# rf-mixer.net
KiCad netlist of a schematic drawn in Altium Designer
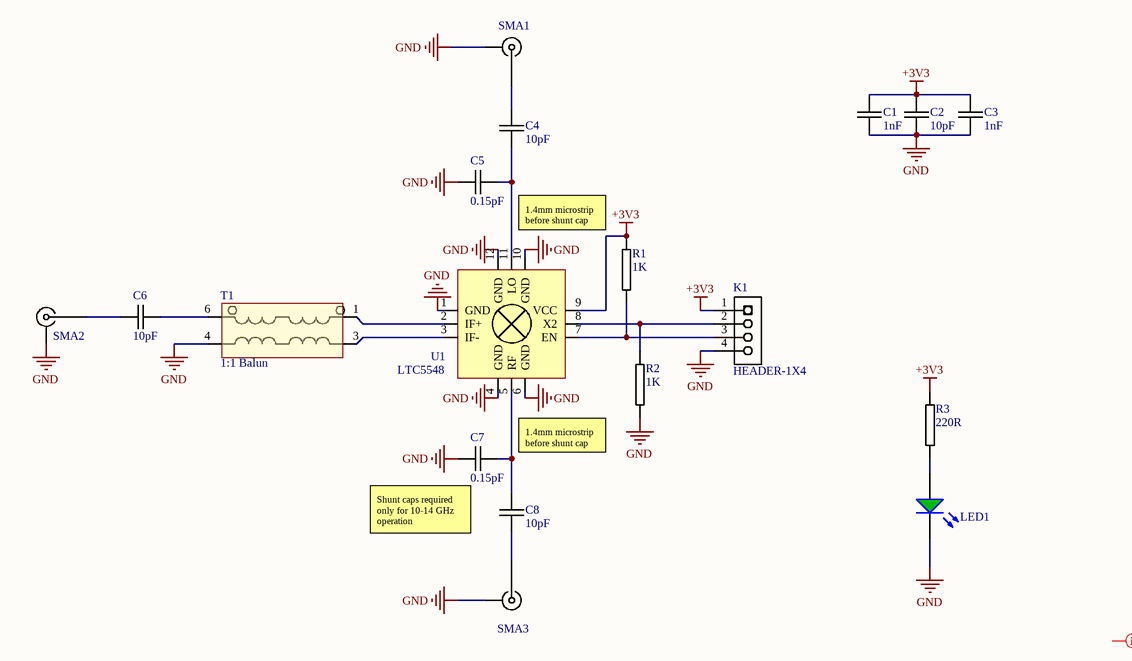
[diagram p0: rf-mixer.SchDoc]

(export (version "E")
  (design (tool "Eeschema 10.0.6"))
  (components
    (comp (ref "C1")
      (value "1nF")
      (footprint "0603C-GENERIC")
      (description "CAPACITOR 0603 CERAMIC")
      (libsource (lib "SMD Capacitors 0603") (part "0603C-1NF-50V-X7R"))
    )
    (comp (ref "C2")
      (value "10pF")
      (footprint "0603C-GENERIC")
      (description "CAPACITOR 0603 CERAMIC")
      (libsource (lib "SMD Capacitors 0603") (part "0603C-10PF-50V-C0G-MUR"))
    )
    (comp (ref "C3")
      (value "1nF")
      (footprint "0603C-GENERIC")
      (description "CAPACITOR 0603 CERAMIC")
      (libsource (lib "SMD Capacitors 0603") (part "0603C-1NF-50V-X7R"))
    )
    (comp (ref "C4")
      (value "10pF")
      (footprint "0603C-GENERIC")
      (description "CAPACITOR 0603 CERAMIC")
      (libsource (lib "SMD Capacitors 0603") (part "0603C-10PF-50V-C0G-MUR"))
    )
    (comp (ref "C5")
      (value "0.15pF")
      (footprint "0603C-GENERIC")
      (description "CAPACITOR 0603 CERAMIC")
      (libsource (lib "SMD Capacitors 0603") (part "0603C-0.15PF-50V-C0G"))
    )
    (comp (ref "C6")
      (value "10pF")
      (footprint "0603C-GENERIC")
      (description "CAPACITOR 0603 CERAMIC")
      (libsource (lib "SMD Capacitors 0603") (part "0603C-10PF-50V-C0G-MUR"))
    )
    (comp (ref "C7")
      (value "0.15pF")
      (footprint "0603C-GENERIC")
      (description "CAPACITOR 0603 CERAMIC")
      (libsource (lib "SMD Capacitors 0603") (part "0603C-0.15PF-50V-C0G"))
    )
    (comp (ref "C8")
      (value "10pF")
      (footprint "0603C-GENERIC")
      (description "CAPACITOR 0603 CERAMIC")
      (libsource (lib "SMD Capacitors 0603") (part "0603C-10PF-50V-C0G-MUR"))
    )
    (comp (ref "K1")
      (value "HEADER-1X4")
      (footprint "HEADER-1X4")
      (libsource (lib "TH Connectors") (part "HEADER-1X4"))
    )
    (comp (ref "LED1")
      (value "Green")
      (footprint "0805LED - GREEN")
      (libsource (lib "custom_parts_old") (part "0805 SMD LED - GREEN"))
    )
    (comp (ref "R1")
      (value "1K")
      (footprint "0603R-1k")
      (description "GENERIC RESISTOR 0603")
      (fields
        (field (name "MANUFACTURER PART NUMBER") "RMCF 1/16 1K 1% R")
        (field (name "MANUFACTURER") "Stackpole Electronics Inc")
      )
      (libsource (lib "SMD Resistors 0603") (part "0603R-1K"))
    )
    (comp (ref "R2")
      (value "1K")
      (footprint "0603R-1k")
      (description "GENERIC RESISTOR 0603")
      (fields
        (field (name "MANUFACTURER PART NUMBER") "RMCF 1/16 1K 1% R")
        (field (name "MANUFACTURER") "Stackpole Electronics Inc")
      )
      (libsource (lib "SMD Resistors 0603") (part "0603R-1K"))
    )
    (comp (ref "R3")
      (value "220R")
      (footprint "0603R-220")
      (description "GENERIC RESISTOR 0603")
      (fields
        (field (name "MANUFACTURER") "Stackpole Electronics Inc")
        (field (name "MANUFACTURER PART NUMBER") "RMCF 1/16 220 1% R")
      )
      (libsource (lib "SMD Resistors 0603") (part "0603R-220"))
    )
    (comp (ref "SMA1")
      (value "*")
      (footprint "MOLEX_SMA_EDGE")
      (libsource (lib "rf_new") (part "MOLEX_SMA_EDGE"))
    )
    (comp (ref "SMA2")
      (value "*")
      (footprint "MOLEX_SMA_EDGE")
      (libsource (lib "rf_new") (part "MOLEX_SMA_EDGE"))
    )
    (comp (ref "SMA3")
      (value "*")
      (footprint "MOLEX_SMA_EDGE")
      (libsource (lib "") (part "MOLEX_SMA_EDGE_1"))
    )
    (comp (ref "T1")
      (value "1:1 Balun")
      (footprint "TC1-1-13M+_FOOTPRINT")
      (libsource (lib "rf_new") (part "TC1-1-13M+ 1{colon}1 RF Balun"))
    )
    (comp (ref "U1")
      (value "LTC5548")
      (footprint "LTC5548_QFN3mmx2mm")
      (libsource (lib "rf_new") (part "LTC5548"))
    )
  )
  (nets
    (net (code "1") (name "+3V3") (class "Default")
      (node (ref "C1") (pin "2") (pintype "passive"))
      (node (ref "C2") (pin "2") (pintype "passive"))
      (node (ref "C3") (pin "2") (pintype "passive"))
      (node (ref "K1") (pin "1") (pintype "passive"))
      (node (ref "R1") (pin "2") (pintype "passive"))
      (node (ref "R3") (pin "1") (pintype "passive"))
      (node (ref "U1") (pin "9") (pinfunction "VCC_9") (pintype "passive"))
    )
    (net (code "2") (name "GND") (class "Default")
      (node (ref "C1") (pin "1") (pintype "passive"))
      (node (ref "C2") (pin "1") (pintype "passive"))
      (node (ref "C3") (pin "1") (pintype "passive"))
      (node (ref "C5") (pin "1") (pintype "passive"))
      (node (ref "C7") (pin "1") (pintype "passive"))
      (node (ref "K1") (pin "4") (pintype "passive"))
      (node (ref "LED1") (pin "K") (pinfunction "K_K") (pintype "passive"))
      (node (ref "R2") (pin "1") (pintype "passive"))
      (node (ref "SMA1") (pin "2") (pinfunction "2_2") (pintype "passive"))
      (node (ref "SMA2") (pin "2") (pinfunction "2_2") (pintype "passive"))
      (node (ref "SMA3") (pin "2") (pinfunction "2_2") (pintype "passive"))
      (node (ref "T1") (pin "4") (pinfunction "GND_4") (pintype "passive"))
      (node (ref "U1") (pin "1") (pinfunction "GND_1") (pintype "passive"))
      (node (ref "U1") (pin "10") (pinfunction "GND_10") (pintype "passive"))
      (node (ref "U1") (pin "12") (pinfunction "GND_12") (pintype "passive"))
      (node (ref "U1") (pin "4") (pinfunction "GND_4") (pintype "passive"))
      (node (ref "U1") (pin "6") (pinfunction "GND_6") (pintype "passive"))
    )
    (net (code "3") (name "Net-(C4-Pad2)") (class "Default")
      (node (ref "C4") (pin "2") (pintype "passive"))
      (node (ref "SMA1") (pin "1") (pinfunction "1_1") (pintype "passive"))
    )
    (net (code "4") (name "Net-(C6-Pad1)") (class "Default")
      (node (ref "C6") (pin "1") (pintype "passive"))
      (node (ref "T1") (pin "6") (pinfunction "GND_6") (pintype "passive"))
    )
    (net (code "5") (name "Net-(C6-Pad2)") (class "Default")
      (node (ref "C6") (pin "2") (pintype "passive"))
      (node (ref "SMA2") (pin "1") (pinfunction "1_1") (pintype "passive"))
    )
    (net (code "6") (name "Net-(C8-Pad1)") (class "Default")
      (node (ref "C8") (pin "1") (pintype "passive"))
      (node (ref "SMA3") (pin "1") (pinfunction "1_1") (pintype "passive"))
    )
    (net (code "7") (name "Net-(LED1-PadA)") (class "Default")
      (node (ref "LED1") (pin "A") (pinfunction "A_A") (pintype "passive"))
      (node (ref "R3") (pin "2") (pintype "passive"))
    )
    (net (code "8") (name "Net-(U1-EN)") (class "Default")
      (node (ref "K1") (pin "3") (pintype "passive"))
      (node (ref "R1") (pin "1") (pintype "passive"))
      (node (ref "U1") (pin "7") (pinfunction "EN_7") (pintype "passive"))
    )
    (net (code "9") (name "Net-(U1-IF+)") (class "Default")
      (node (ref "T1") (pin "1") (pinfunction "GND_1") (pintype "passive"))
      (node (ref "U1") (pin "2") (pinfunction "IF+_2") (pintype "passive"))
    )
    (net (code "10") (name "Net-(U1-IF-)") (class "Default")
      (node (ref "T1") (pin "3") (pinfunction "GND_3") (pintype "passive"))
      (node (ref "U1") (pin "3") (pinfunction "IF-_3") (pintype "passive"))
    )
    (net (code "11") (name "Net-(U1-LO)") (class "Default")
      (node (ref "C4") (pin "1") (pintype "passive"))
      (node (ref "C5") (pin "2") (pintype "passive"))
      (node (ref "U1") (pin "11") (pinfunction "LO_11") (pintype "passive"))
    )
    (net (code "12") (name "Net-(U1-RF)") (class "Default")
      (node (ref "C7") (pin "2") (pintype "passive"))
      (node (ref "C8") (pin "2") (pintype "passive"))
      (node (ref "U1") (pin "5") (pinfunction "RF_5") (pintype "passive"))
    )
    (net (code "13") (name "Net-(U1-X2)") (class "Default")
      (node (ref "K1") (pin "2") (pintype "passive"))
      (node (ref "R2") (pin "2") (pintype "passive"))
      (node (ref "U1") (pin "8") (pinfunction "X2_8") (pintype "passive"))
    )
  )
)
